# Outputs.net
KiCad netlist of a schematic drawn in Altium Designer
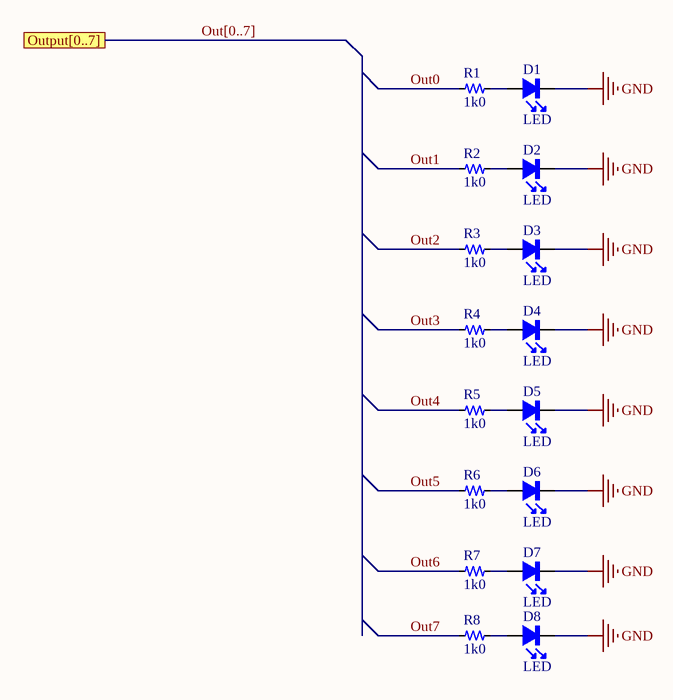
[diagram p0: Outputs.SchDoc]

(export (version "E")
  (design (tool "Eeschema 10.0.6"))
  (components
    (comp (ref "D1")
      (value "LED")
      (footprint "LED-0805")
      (description "LED - Light-Emitting Diode")
      (libsource (lib "RasUNMSM") (part "LED"))
    )
    (comp (ref "D2")
      (value "LED")
      (footprint "LED-0805")
      (description "LED - Light-Emitting Diode")
      (libsource (lib "RasUNMSM") (part "LED"))
    )
    (comp (ref "D3")
      (value "LED")
      (footprint "LED-0805")
      (description "LED - Light-Emitting Diode")
      (libsource (lib "RasUNMSM") (part "LED"))
    )
    (comp (ref "D4")
      (value "LED")
      (footprint "LED-0805")
      (description "LED - Light-Emitting Diode")
      (libsource (lib "RasUNMSM") (part "LED"))
    )
    (comp (ref "D5")
      (value "LED")
      (footprint "LED-0805")
      (description "LED - Light-Emitting Diode")
      (libsource (lib "RasUNMSM") (part "LED"))
    )
    (comp (ref "D6")
      (value "LED")
      (footprint "LED-0805")
      (description "LED - Light-Emitting Diode")
      (libsource (lib "RasUNMSM") (part "LED"))
    )
    (comp (ref "D7")
      (value "LED")
      (footprint "LED-0805")
      (description "LED - Light-Emitting Diode")
      (libsource (lib "RasUNMSM") (part "LED"))
    )
    (comp (ref "D8")
      (value "LED")
      (footprint "LED-0805")
      (description "LED - Light-Emitting Diode")
      (libsource (lib "RasUNMSM") (part "LED"))
    )
    (comp (ref "R1")
      (value "1k0")
      (footprint "R0805")
      (description "Single resistor")
      (fields (field (name "POWER") "0.125W"))
      (libsource (lib "RasUNMSM") (part "Resistor"))
    )
    (comp (ref "R2")
      (value "1k0")
      (footprint "R0805")
      (description "Single resistor")
      (fields (field (name "POWER") "0.125W"))
      (libsource (lib "RasUNMSM") (part "Resistor"))
    )
    (comp (ref "R3")
      (value "1k0")
      (footprint "R0805")
      (description "Single resistor")
      (fields (field (name "POWER") "0.125W"))
      (libsource (lib "RasUNMSM") (part "Resistor"))
    )
    (comp (ref "R4")
      (value "1k0")
      (footprint "R0805")
      (description "Single resistor")
      (fields (field (name "POWER") "0.125W"))
      (libsource (lib "RasUNMSM") (part "Resistor"))
    )
    (comp (ref "R5")
      (value "1k0")
      (footprint "R0805")
      (description "Single resistor")
      (fields (field (name "POWER") "0.125W"))
      (libsource (lib "RasUNMSM") (part "Resistor"))
    )
    (comp (ref "R6")
      (value "1k0")
      (footprint "R0805")
      (description "Single resistor")
      (fields (field (name "POWER") "0.125W"))
      (libsource (lib "RasUNMSM") (part "Resistor"))
    )
    (comp (ref "R7")
      (value "1k0")
      (footprint "R0805")
      (description "Single resistor")
      (fields (field (name "POWER") "0.125W"))
      (libsource (lib "RasUNMSM") (part "Resistor"))
    )
    (comp (ref "R8")
      (value "1k0")
      (footprint "R0805")
      (description "Single resistor")
      (fields (field (name "POWER") "0.125W"))
      (libsource (lib "RasUNMSM") (part "Resistor"))
    )
  )
  (nets
    (net (code "1") (name "/Out0") (class "Default")
      (node (ref "R1") (pin "2") (pinfunction "2_2") (pintype "passive"))
    )
    (net (code "2") (name "/Out1") (class "Default")
      (node (ref "R2") (pin "2") (pinfunction "2_2") (pintype "passive"))
    )
    (net (code "3") (name "/Out2") (class "Default")
      (node (ref "R3") (pin "2") (pinfunction "2_2") (pintype "passive"))
    )
    (net (code "4") (name "/Out3") (class "Default")
      (node (ref "R4") (pin "2") (pinfunction "2_2") (pintype "passive"))
    )
    (net (code "5") (name "/Out4") (class "Default")
      (node (ref "R5") (pin "2") (pinfunction "2_2") (pintype "passive"))
    )
    (net (code "6") (name "/Out5") (class "Default")
      (node (ref "R6") (pin "2") (pinfunction "2_2") (pintype "passive"))
    )
    (net (code "7") (name "/Out6") (class "Default")
      (node (ref "R7") (pin "2") (pinfunction "2_2") (pintype "passive"))
    )
    (net (code "8") (name "/Out7") (class "Default")
      (node (ref "R8") (pin "2") (pinfunction "2_2") (pintype "passive"))
    )
    (net (code "10") (name "GND") (class "Default")
      (node (ref "D1") (pin "1") (pinfunction "1_1") (pintype "passive"))
      (node (ref "D2") (pin "1") (pinfunction "1_1") (pintype "passive"))
      (node (ref "D3") (pin "1") (pinfunction "1_1") (pintype "passive"))
      (node (ref "D4") (pin "1") (pinfunction "1_1") (pintype "passive"))
      (node (ref "D5") (pin "1") (pinfunction "1_1") (pintype "passive"))
      (node (ref "D6") (pin "1") (pinfunction "1_1") (pintype "passive"))
      (node (ref "D7") (pin "1") (pinfunction "1_1") (pintype "passive"))
      (node (ref "D8") (pin "1") (pinfunction "1_1") (pintype "passive"))
    )
    (net (code "11") (name "Net-(D1-Pad2)") (class "Default")
      (node (ref "D1") (pin "2") (pinfunction "2_2") (pintype "passive"))
      (node (ref "R1") (pin "1") (pinfunction "1_1") (pintype "passive"))
    )
    (net (code "12") (name "Net-(D2-Pad2)") (class "Default")
      (node (ref "D2") (pin "2") (pinfunction "2_2") (pintype "passive"))
      (node (ref "R2") (pin "1") (pinfunction "1_1") (pintype "passive"))
    )
    (net (code "13") (name "Net-(D3-Pad2)") (class "Default")
      (node (ref "D3") (pin "2") (pinfunction "2_2") (pintype "passive"))
      (node (ref "R3") (pin "1") (pinfunction "1_1") (pintype "passive"))
    )
    (net (code "14") (name "Net-(D4-Pad2)") (class "Default")
      (node (ref "D4") (pin "2") (pinfunction "2_2") (pintype "passive"))
      (node (ref "R4") (pin "1") (pinfunction "1_1") (pintype "passive"))
    )
    (net (code "15") (name "Net-(D5-Pad2)") (class "Default")
      (node (ref "D5") (pin "2") (pinfunction "2_2") (pintype "passive"))
      (node (ref "R5") (pin "1") (pinfunction "1_1") (pintype "passive"))
    )
    (net (code "16") (name "Net-(D6-Pad2)") (class "Default")
      (node (ref "D6") (pin "2") (pinfunction "2_2") (pintype "passive"))
      (node (ref "R6") (pin "1") (pinfunction "1_1") (pintype "passive"))
    )
    (net (code "17") (name "Net-(D7-Pad2)") (class "Default")
      (node (ref "D7") (pin "2") (pinfunction "2_2") (pintype "passive"))
      (node (ref "R7") (pin "1") (pinfunction "1_1") (pintype "passive"))
    )
    (net (code "18") (name "Net-(D8-Pad2)") (class "Default")
      (node (ref "D8") (pin "2") (pinfunction "2_2") (pintype "passive"))
      (node (ref "R8") (pin "1") (pinfunction "1_1") (pintype "passive"))
    )
  )
)
